# full.net
KiCad netlist of a schematic drawn in Altium Designer
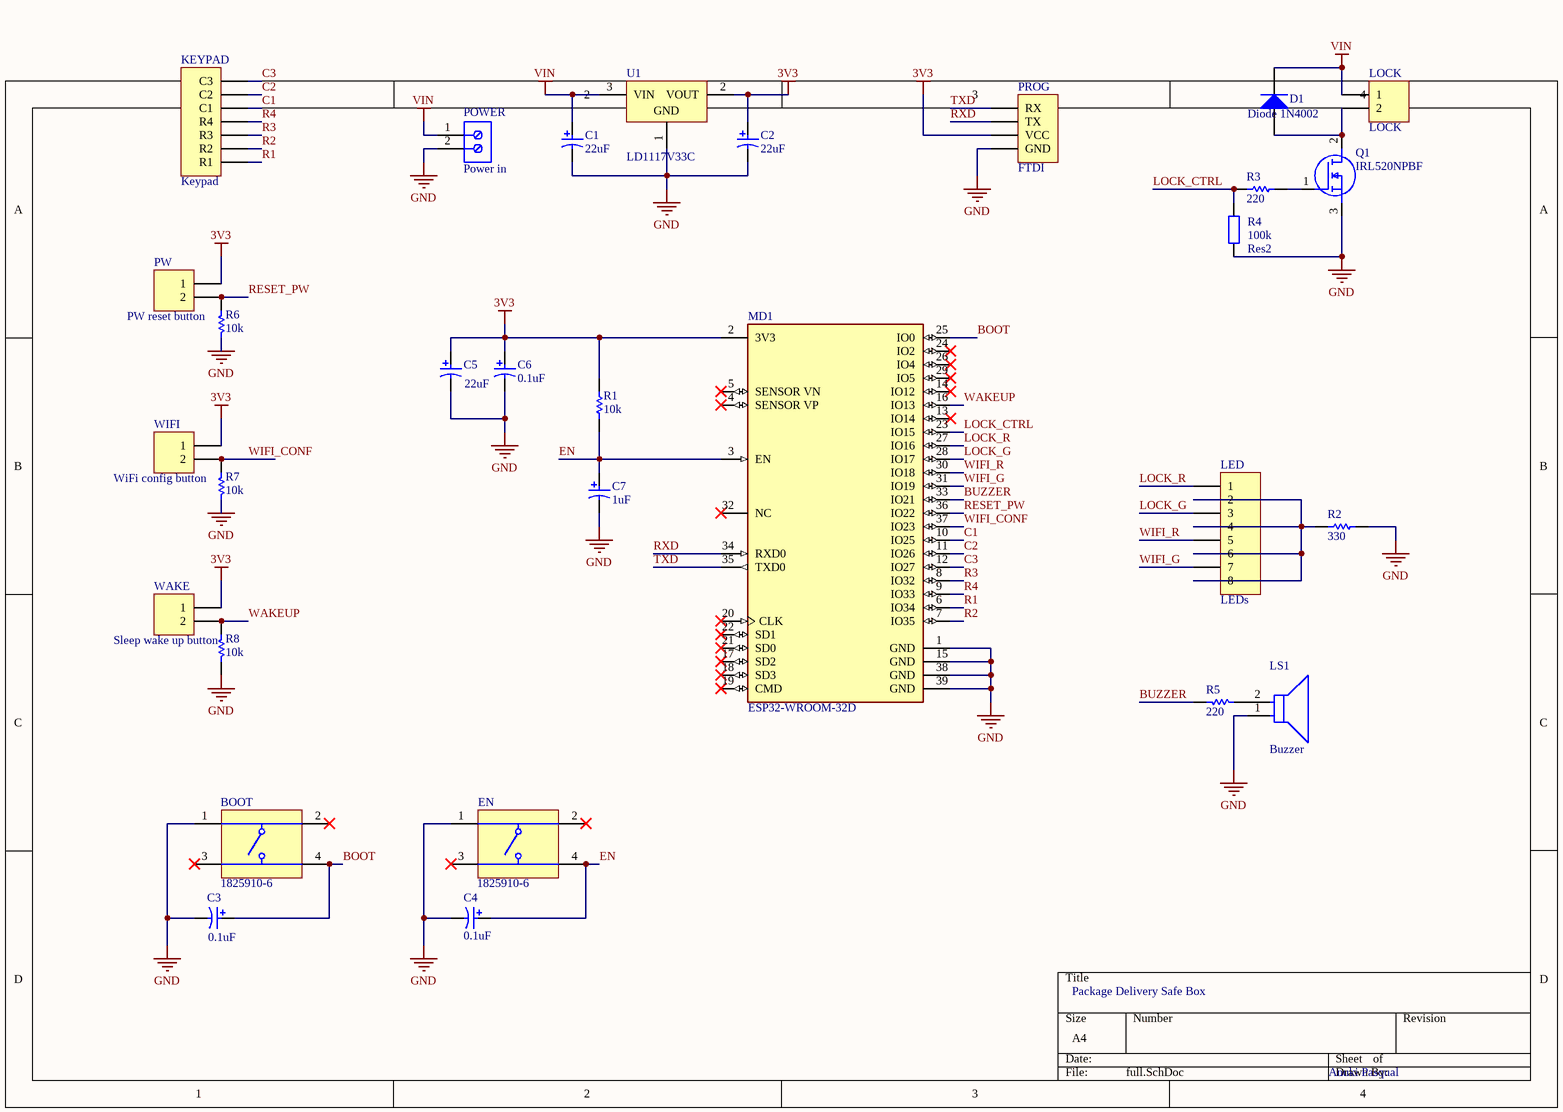
[diagram p0: full.SchDoc]

(export (version "E")
  (design (tool "Eeschema 10.0.6"))
  (components
    (comp (ref "BOOT")
      (value "1825910-6")
      (footprint "TECO-1825910-6_V")
      (description "Tact Switch, SPST-NO, 0.05 A, -35 to 85 degC, 4-Pin THD, RoHS, Bulk")
      (fields (field (name "MANUFACTURER") "TE Connectivity"))
      (libsource (lib "Altium Content Vault") (part "SW-SPST-4_A"))
    )
    (comp (ref "C1")
      (value "22uF")
      (footprint "CAPPR55-200-1100X500X1200")
      (description "Aluminum Electrolytic Capacitor, 22 uF, +/- 20%, 50 V, -40 to 85 degC, 2-Pin THD, RoHS, Bulk")
      (fields (field (name "VOLTAGE") "50V") (field (name "MANUFACTURER") "Panasonic"))
      (libsource (lib "Altium Content Vault") (part "CAP-P-2"))
    )
    (comp (ref "C2")
      (value "22uF")
      (footprint "CAPPR55-200-1100X500X1200")
      (description "Aluminum Electrolytic Capacitor, 22 uF, +/- 20%, 50 V, -40 to 85 degC, 2-Pin THD, RoHS, Bulk")
      (fields (field (name "VOLTAGE") "50V") (field (name "MANUFACTURER") "Panasonic"))
      (libsource (lib "Altium Content Vault") (part "CAP-P-2"))
    )
    (comp (ref "C3")
      (value "0.1uF")
      (footprint "CAPPR55-200-1100X500X1200")
      (description "Aluminum Electrolytic Capacitor, 22 uF, +/- 20%, 50 V, -40 to 85 degC, 2-Pin THD, RoHS, Bulk")
      (fields (field (name "VOLTAGE") "50V") (field (name "MANUFACTURER") "Panasonic"))
      (libsource (lib "Altium Content Vault") (part "CAP-P-2"))
    )
    (comp (ref "C4")
      (value "0.1uF")
      (footprint "CAPPR55-200-1100X500X1200")
      (description "Aluminum Electrolytic Capacitor, 22 uF, +/- 20%, 50 V, -40 to 85 degC, 2-Pin THD, RoHS, Bulk")
      (fields (field (name "VOLTAGE") "50V") (field (name "MANUFACTURER") "Panasonic"))
      (libsource (lib "Altium Content Vault") (part "CAP-P-2"))
    )
    (comp (ref "C5")
      (value "22uF")
      (footprint "CAPPR55-200-1100X500X1200")
      (description "Aluminum Electrolytic Capacitor, 22 uF, +/- 20%, 50 V, -40 to 85 degC, 2-Pin THD, RoHS, Bulk")
      (fields (field (name "VOLTAGE") "50V") (field (name "MANUFACTURER") "Panasonic"))
      (libsource (lib "Altium Content Vault") (part "CAP-P-2"))
    )
    (comp (ref "C6")
      (value "0.1uF")
      (footprint "CAPPR55-200-1100X500X1200")
      (description "Aluminum Electrolytic Capacitor, 22 uF, +/- 20%, 50 V, -40 to 85 degC, 2-Pin THD, RoHS, Bulk")
      (fields (field (name "VOLTAGE") "50V") (field (name "MANUFACTURER") "Panasonic"))
      (libsource (lib "Altium Content Vault") (part "CAP-P-2"))
    )
    (comp (ref "C7")
      (value "1uF")
      (footprint "CAPPR55-200-1100X500X1200")
      (description "Aluminum Electrolytic Capacitor, 22 uF, +/- 20%, 50 V, -40 to 85 degC, 2-Pin THD, RoHS, Bulk")
      (fields (field (name "VOLTAGE") "50V") (field (name "MANUFACTURER") "Panasonic"))
      (libsource (lib "Altium Content Vault") (part "CAP-P-2"))
    )
    (comp (ref "D1")
      (value "Diode 1N4002")
      (footprint "DO-41")
      (description "1 Amp General Purpose Rectifier")
      (fields (field (name "PUBLISHER") "Altium Limited"))
      (libsource (lib "Miscellaneous Devices") (part "Diode 1N4002"))
    )
    (comp (ref "EN")
      (value "1825910-6")
      (footprint "TECO-1825910-6_V")
      (description "Tact Switch, SPST-NO, 0.05 A, -35 to 85 degC, 4-Pin THD, RoHS, Bulk")
      (fields (field (name "MANUFACTURER") "TE Connectivity"))
      (libsource (lib "Altium Content Vault") (part "SW-SPST-4_A"))
    )
    (comp (ref "KEYPAD")
      (value "Keypad")
      (footprint "Miscellaneous Connectors:HDR1X7")
      (description "Header, 7-Pin")
      (fields (field (name "PUBLISHER") "Altium Limited"))
      (libsource (lib "Miscellaneous Connectors") (part "Header 7"))
    )
    (comp (ref "LED")
      (value "LEDs")
      (footprint "HDR1X8")
      (description "Header, 8-Pin")
      (fields (field (name "PUBLISHER") "Altium Limited"))
      (libsource (lib "Miscellaneous Connectors") (part "Header 8"))
    )
    (comp (ref "LOCK")
      (value "LOCK")
      (footprint "HDR1X2")
      (description "Header, 2-Pin")
      (fields (field (name "PUBLISHER") "Altium Limited"))
      (libsource (lib "") (part "Header 2_1"))
    )
    (comp (ref "LS1")
      (value "Buzzer")
      (footprint "FP-MCKPX-G1203A-K4056-MFG")
      (description "MAGNETIC BUZZER AND TRANSDUCER - More Details")
      (fields
        (field (name "MANUFACTURER PART NUMBER") "MCKPX-G1203A-K4056")
        (field (name "MANUFACTURER") "Multicomp Pro")
      )
      (libsource (lib "Altium Content Vault") (part "1973c4b650225fd2ddacaff6b763965"))
    )
    (comp (ref "MD1")
      (value "ESP32-WROOM-32D")
      (footprint "FP-ESP32-WROOM-32D-MFG")
      (description "WIFI MODULE 32MBITS SPI FLASH")
      (fields
        (field (name "OCTOPART") "https://octopart.com/esp32-wroom-32d-espressif+systems-91040050")
        (field (name "MANUFACTURER") "Espressif Systems")
      )
      (libsource (lib "Altium Content Vault") (part "a031a76f8c27026a7a7f4657ff233a3"))
    )
    (comp (ref "POWER")
      (value "Power in")
      (footprint "691102710002")
      (description "Series 102 - 5.00 mm Horizontal Entry Modular with Pressure Clamp WR-TBL, 2 pin")
      (fields
        (field (name "MANUFACTURER") "Wurth Elektronik")
        (field (name "PART NUMBER") "691102710002")
        (field (name "PUBLISHER") "WurthElektronik")
      )
      (libsource (lib "Altium Content Vault") (part "WE-CN-1P-F-TB2"))
    )
    (comp (ref "PROG")
      (value "FTDI")
      (footprint "HDR1X4")
      (description "Header, 4-Pin")
      (fields (field (name "PUBLISHER") "Altium Limited"))
      (libsource (lib "Miscellaneous Connectors") (part "Header 4"))
    )
    (comp (ref "PW")
      (value "PW reset button")
      (footprint "HDR1X2")
      (description "Header, 2-Pin")
      (fields (field (name "PUBLISHER") "Altium Limited"))
      (libsource (lib "Miscellaneous Connectors") (part "Header 2"))
    )
    (comp (ref "Q1")
      (value "IRL520NPBF")
      (footprint "SamacSys:TO254P469X1042X1967-3P")
      (description "MOSFET (N-Channel)")
      (fields (field (name "MOUSER PART NUMBER") "942-IRL520NPBF"))
      (libsource (lib "SamacSys") (part "IRL520NPBF"))
    )
    (comp (ref "R1")
      (value "10k")
      (footprint "AXIAL-0.3")
      (description "Resistor")
      (fields (field (name "PUBLISHER") "Altium Limited"))
      (libsource (lib "Miscellaneous Devices") (part "Res1"))
    )
    (comp (ref "R2")
      (value "330")
      (footprint "AXIAL-0.3")
      (description "Resistor")
      (fields (field (name "PUBLISHER") "Altium Limited"))
      (libsource (lib "Miscellaneous Devices") (part "Res1"))
    )
    (comp (ref "R3")
      (value "220")
      (footprint "AXIAL-0.3")
      (description "Resistor")
      (fields (field (name "PUBLISHER") "Altium Limited"))
      (libsource (lib "Miscellaneous Devices") (part "Res1"))
    )
    (comp (ref "R4")
      (value "Res2")
      (footprint "AXIAL-0.4")
      (description "Resistor")
      (fields (field (name "ALTIUM_VALUE") "100k") (field (name "PUBLISHER") "Altium Limited"))
      (libsource (lib "Miscellaneous Devices") (part "Res2"))
    )
    (comp (ref "R5")
      (value "220")
      (footprint "AXIAL-0.3")
      (description "Resistor")
      (fields (field (name "PUBLISHER") "Altium Limited"))
      (libsource (lib "Miscellaneous Devices") (part "Res1"))
    )
    (comp (ref "R6")
      (value "10k")
      (footprint "AXIAL-0.3")
      (description "Resistor")
      (fields (field (name "PUBLISHER") "Altium Limited"))
      (libsource (lib "Miscellaneous Devices") (part "Res1"))
    )
    (comp (ref "R7")
      (value "10k")
      (footprint "AXIAL-0.3")
      (description "Resistor")
      (fields (field (name "PUBLISHER") "Altium Limited"))
      (libsource (lib "Miscellaneous Devices") (part "Res1"))
    )
    (comp (ref "R8")
      (value "10k")
      (footprint "AXIAL-0.3")
      (description "Resistor")
      (fields (field (name "PUBLISHER") "Altium Limited"))
      (libsource (lib "Miscellaneous Devices") (part "Res1"))
    )
    (comp (ref "U1")
      (value "LD1117V33C")
      (footprint "TO220")
      (description "Fixed Low Drop Positive Voltage Regulator, 3.3V, 3-Pin TO-220")
      (libsource (lib "Altium Content Vault") (part "PM-REG-LD1117V-SIL3"))
    )
    (comp (ref "WAKE")
      (value "Sleep wake up button")
      (footprint "HDR1X2")
      (description "Header, 2-Pin")
      (fields (field (name "PUBLISHER") "Altium Limited"))
      (libsource (lib "Miscellaneous Connectors") (part "Header 2"))
    )
    (comp (ref "WIFI")
      (value "WiFi config button")
      (footprint "HDR1X2")
      (description "Header, 2-Pin")
      (fields (field (name "PUBLISHER") "Altium Limited"))
      (libsource (lib "Miscellaneous Connectors") (part "Header 2"))
    )
  )
  (nets
    (net (code "1") (name "/BOOT") (class "Default")
      (node (ref "BOOT") (pin "4") (pinfunction "4_4") (pintype "passive"))
      (node (ref "C3") (pin "1") (pinfunction "1_1") (pintype "passive"))
      (node (ref "MD1") (pin "25") (pinfunction "IO0_25") (pintype "bidirectional"))
    )
    (net (code "2") (name "/BUZZER") (class "Default")
      (node (ref "MD1") (pin "33") (pinfunction "IO21_33") (pintype "bidirectional"))
      (node (ref "R5") (pin "1") (pinfunction "1_1") (pintype "passive"))
    )
    (net (code "3") (name "/C1") (class "Default")
      (node (ref "KEYPAD") (pin "5") (pinfunction "C1_5") (pintype "passive"))
      (node (ref "MD1") (pin "10") (pinfunction "IO25_10") (pintype "bidirectional"))
    )
    (net (code "4") (name "/C2") (class "Default")
      (node (ref "KEYPAD") (pin "6") (pinfunction "C2_6") (pintype "passive"))
      (node (ref "MD1") (pin "11") (pinfunction "IO26_11") (pintype "bidirectional"))
    )
    (net (code "5") (name "/C3") (class "Default")
      (node (ref "KEYPAD") (pin "7") (pinfunction "C3_7") (pintype "passive"))
      (node (ref "MD1") (pin "12") (pinfunction "IO27_12") (pintype "bidirectional"))
    )
    (net (code "6") (name "/EN") (class "Default")
      (node (ref "C4") (pin "1") (pinfunction "1_1") (pintype "passive"))
      (node (ref "C7") (pin "1") (pinfunction "1_1") (pintype "passive"))
      (node (ref "EN") (pin "4") (pinfunction "4_4") (pintype "passive"))
      (node (ref "MD1") (pin "3") (pinfunction "EN_3") (pintype "input"))
      (node (ref "R1") (pin "1") (pinfunction "1_1") (pintype "passive"))
    )
    (net (code "7") (name "/LOCK_CTRL") (class "Default")
      (node (ref "MD1") (pin "23") (pinfunction "IO15_23") (pintype "bidirectional"))
      (node (ref "R3") (pin "2") (pinfunction "2_2") (pintype "passive"))
      (node (ref "R4") (pin "2") (pinfunction "2_2") (pintype "passive"))
    )
    (net (code "8") (name "/LOCK_G") (class "Default")
      (node (ref "LED") (pin "3") (pinfunction "3_3") (pintype "passive"))
      (node (ref "MD1") (pin "28") (pinfunction "IO17_28") (pintype "bidirectional"))
    )
    (net (code "9") (name "/LOCK_R") (class "Default")
      (node (ref "LED") (pin "1") (pinfunction "1_1") (pintype "passive"))
      (node (ref "MD1") (pin "27") (pinfunction "IO16_27") (pintype "bidirectional"))
    )
    (net (code "10") (name "/R1") (class "Default")
      (node (ref "KEYPAD") (pin "1") (pinfunction "R1_1") (pintype "passive"))
      (node (ref "MD1") (pin "6") (pinfunction "IO34_6") (pintype "bidirectional"))
    )
    (net (code "11") (name "/R2") (class "Default")
      (node (ref "KEYPAD") (pin "2") (pinfunction "R2_2") (pintype "passive"))
      (node (ref "MD1") (pin "7") (pinfunction "IO35_7") (pintype "bidirectional"))
    )
    (net (code "12") (name "/R3") (class "Default")
      (node (ref "KEYPAD") (pin "3") (pinfunction "R3_3") (pintype "passive"))
      (node (ref "MD1") (pin "8") (pinfunction "IO32_8") (pintype "bidirectional"))
    )
    (net (code "13") (name "/R4") (class "Default")
      (node (ref "KEYPAD") (pin "4") (pinfunction "R4_4") (pintype "passive"))
      (node (ref "MD1") (pin "9") (pinfunction "IO33_9") (pintype "bidirectional"))
    )
    (net (code "14") (name "/RESET_PW") (class "Default")
      (node (ref "MD1") (pin "36") (pinfunction "IO22_36") (pintype "bidirectional"))
      (node (ref "PW") (pin "2") (pinfunction "2_2") (pintype "passive"))
      (node (ref "R6") (pin "1") (pinfunction "1_1") (pintype "passive"))
    )
    (net (code "15") (name "/RXD") (class "Default")
      (node (ref "MD1") (pin "34") (pinfunction "RXD0_34") (pintype "input"))
      (node (ref "PROG") (pin "2") (pinfunction "TX_2") (pintype "passive"))
    )
    (net (code "16") (name "/TXD") (class "Default")
      (node (ref "MD1") (pin "35") (pinfunction "TXD0_35") (pintype "output"))
      (node (ref "PROG") (pin "1") (pinfunction "RX_1") (pintype "passive"))
    )
    (net (code "17") (name "/WAKEUP") (class "Default")
      (node (ref "MD1") (pin "16") (pinfunction "IO13_16") (pintype "bidirectional"))
      (node (ref "R8") (pin "1") (pinfunction "1_1") (pintype "passive"))
      (node (ref "WAKE") (pin "2") (pinfunction "2_2") (pintype "passive"))
    )
    (net (code "18") (name "/WIFI_CONF") (class "Default")
      (node (ref "MD1") (pin "37") (pinfunction "IO23_37") (pintype "bidirectional"))
      (node (ref "R7") (pin "1") (pinfunction "1_1") (pintype "passive"))
      (node (ref "WIFI") (pin "2") (pinfunction "2_2") (pintype "passive"))
    )
    (net (code "19") (name "/WIFI_G") (class "Default")
      (node (ref "LED") (pin "7") (pinfunction "7_7") (pintype "passive"))
      (node (ref "MD1") (pin "31") (pinfunction "IO19_31") (pintype "bidirectional"))
    )
    (net (code "20") (name "/WIFI_R") (class "Default")
      (node (ref "LED") (pin "5") (pinfunction "5_5") (pintype "passive"))
      (node (ref "MD1") (pin "30") (pinfunction "IO18_30") (pintype "bidirectional"))
    )
    (net (code "21") (name "3V3") (class "Default")
      (node (ref "C2") (pin "1") (pinfunction "1_1") (pintype "passive"))
      (node (ref "C5") (pin "1") (pinfunction "1_1") (pintype "passive"))
      (node (ref "C6") (pin "1") (pinfunction "1_1") (pintype "passive"))
      (node (ref "MD1") (pin "2") (pinfunction "3V3_2") (pintype "power_in"))
      (node (ref "PROG") (pin "3") (pinfunction "VCC_3") (pintype "passive"))
      (node (ref "PW") (pin "1") (pinfunction "1_1") (pintype "passive"))
      (node (ref "R1") (pin "2") (pinfunction "2_2") (pintype "passive"))
      (node (ref "U1") (pin "2") (pinfunction "VOUT_2") (pintype "power_in"))
      (node (ref "WAKE") (pin "1") (pinfunction "1_1") (pintype "passive"))
      (node (ref "WIFI") (pin "1") (pinfunction "1_1") (pintype "passive"))
    )
    (net (code "22") (name "GND") (class "Default")
      (node (ref "BOOT") (pin "1") (pinfunction "1_1") (pintype "passive"))
      (node (ref "C1") (pin "2") (pinfunction "2_2") (pintype "passive"))
      (node (ref "C2") (pin "2") (pinfunction "2_2") (pintype "passive"))
      (node (ref "C3") (pin "2") (pinfunction "2_2") (pintype "passive"))
      (node (ref "C4") (pin "2") (pinfunction "2_2") (pintype "passive"))
      (node (ref "C5") (pin "2") (pinfunction "2_2") (pintype "passive"))
      (node (ref "C6") (pin "2") (pinfunction "2_2") (pintype "passive"))
      (node (ref "C7") (pin "2") (pinfunction "2_2") (pintype "passive"))
      (node (ref "EN") (pin "1") (pinfunction "1_1") (pintype "passive"))
      (node (ref "LS1") (pin "1") (pinfunction "C_1") (pintype "passive"))
      (node (ref "MD1") (pin "1") (pinfunction "GND_1") (pintype "power_in"))
      (node (ref "MD1") (pin "15") (pinfunction "GND_15") (pintype "power_in"))
      (node (ref "MD1") (pin "38") (pinfunction "GND_38") (pintype "power_in"))
      (node (ref "MD1") (pin "39") (pinfunction "GND_39") (pintype "power_in"))
      (node (ref "POWER") (pin "2") (pinfunction "2_2") (pintype "passive"))
      (node (ref "PROG") (pin "4") (pinfunction "GND_4") (pintype "passive"))
      (node (ref "Q1") (pin "3") (pinfunction "S_3") (pintype "passive"))
      (node (ref "R2") (pin "2") (pinfunction "2_2") (pintype "passive"))
      (node (ref "R4") (pin "1") (pinfunction "1_1") (pintype "passive"))
      (node (ref "R6") (pin "2") (pinfunction "2_2") (pintype "passive"))
      (node (ref "R7") (pin "2") (pinfunction "2_2") (pintype "passive"))
      (node (ref "R8") (pin "2") (pinfunction "2_2") (pintype "passive"))
      (node (ref "U1") (pin "1") (pinfunction "GND_1") (pintype "power_in"))
    )
    (net (code "23") (name "Net-(D1-A)") (class "Default")
      (node (ref "D1") (pin "1") (pinfunction "A_1") (pintype "passive"))
      (node (ref "LOCK") (pin "2") (pinfunction "2_2") (pintype "passive"))
      (node (ref "Q1") (pin "2") (pinfunction "D_2") (pintype "passive"))
    )
    (net (code "24") (name "Net-(LED-Pad2)") (class "Default")
      (node (ref "LED") (pin "2") (pinfunction "2_2") (pintype "passive"))
      (node (ref "LED") (pin "4") (pinfunction "4_4") (pintype "passive"))
      (node (ref "LED") (pin "6") (pinfunction "6_6") (pintype "passive"))
      (node (ref "LED") (pin "8") (pinfunction "8_8") (pintype "passive"))
      (node (ref "R2") (pin "1") (pinfunction "1_1") (pintype "passive"))
    )
    (net (code "25") (name "Net-(LS1-A)") (class "Default")
      (node (ref "LS1") (pin "2") (pinfunction "A_2") (pintype "passive"))
      (node (ref "R5") (pin "2") (pinfunction "2_2") (pintype "passive"))
    )
    (net (code "26") (name "Net-(Q1-G)") (class "Default")
      (node (ref "Q1") (pin "1") (pinfunction "G_1") (pintype "passive"))
      (node (ref "R3") (pin "1") (pinfunction "1_1") (pintype "passive"))
    )
    (net (code "27") (name "VIN") (class "Default")
      (node (ref "C1") (pin "1") (pinfunction "1_1") (pintype "passive"))
      (node (ref "D1") (pin "2") (pinfunction "K_2") (pintype "passive"))
      (node (ref "LOCK") (pin "1") (pinfunction "1_1") (pintype "passive"))
      (node (ref "POWER") (pin "1") (pinfunction "1_1") (pintype "passive"))
      (node (ref "U1") (pin "3") (pinfunction "VIN_3") (pintype "power_in"))
    )
    (net (code "28") (name "unconnected-(BOOT-Pad2)") (class "Default")
      (node (ref "BOOT") (pin "2") (pinfunction "2_2") (pintype "passive+no_connect"))
    )
    (net (code "29") (name "unconnected-(BOOT-Pad3)") (class "Default")
      (node (ref "BOOT") (pin "3") (pinfunction "3_3") (pintype "passive+no_connect"))
    )
    (net (code "30") (name "unconnected-(EN-Pad2)") (class "Default")
      (node (ref "EN") (pin "2") (pinfunction "2_2") (pintype "passive+no_connect"))
    )
    (net (code "31") (name "unconnected-(EN-Pad3)") (class "Default")
      (node (ref "EN") (pin "3") (pinfunction "3_3") (pintype "passive+no_connect"))
    )
    (net (code "32") (name "unconnected-(MD1-CLK-Pad20)") (class "Default")
      (node (ref "MD1") (pin "20") (pinfunction "CLK_20") (pintype "input+no_connect"))
    )
    (net (code "33") (name "unconnected-(MD1-CMD-Pad19)") (class "Default")
      (node (ref "MD1") (pin "19") (pinfunction "CMD_19") (pintype "bidirectional+no_connect"))
    )
    (net (code "34") (name "unconnected-(MD1-IO2-Pad24)") (class "Default")
      (node (ref "MD1") (pin "24") (pinfunction "IO2_24") (pintype "bidirectional+no_connect"))
    )
    (net (code "35") (name "unconnected-(MD1-IO4-Pad26)") (class "Default")
      (node (ref "MD1") (pin "26") (pinfunction "IO4_26") (pintype "bidirectional+no_connect"))
    )
    (net (code "36") (name "unconnected-(MD1-IO5-Pad29)") (class "Default")
      (node (ref "MD1") (pin "29") (pinfunction "IO5_29") (pintype "bidirectional+no_connect"))
    )
    (net (code "37") (name "unconnected-(MD1-IO12-Pad14)") (class "Default")
      (node (ref "MD1") (pin "14") (pinfunction "IO12_14") (pintype "bidirectional+no_connect"))
    )
    (net (code "38") (name "unconnected-(MD1-IO14-Pad13)") (class "Default")
      (node (ref "MD1") (pin "13") (pinfunction "IO14_13") (pintype "bidirectional+no_connect"))
    )
    (net (code "39") (name "unconnected-(MD1-NC-Pad32)") (class "Default")
      (node (ref "MD1") (pin "32") (pinfunction "NC_32") (pintype "passive+no_connect"))
    )
    (net (code "40") (name "unconnected-(MD1-SD0-Pad21)") (class "Default")
      (node (ref "MD1") (pin "21") (pinfunction "SD0_21") (pintype "bidirectional+no_connect"))
    )
    (net (code "41") (name "unconnected-(MD1-SD1-Pad22)") (class "Default")
      (node (ref "MD1") (pin "22") (pinfunction "SD1_22") (pintype "bidirectional+no_connect"))
    )
    (net (code "42") (name "unconnected-(MD1-SD2-Pad17)") (class "Default")
      (node (ref "MD1") (pin "17") (pinfunction "SD2_17") (pintype "bidirectional+no_connect"))
    )
    (net (code "43") (name "unconnected-(MD1-SD3-Pad18)") (class "Default")
      (node (ref "MD1") (pin "18") (pinfunction "SD3_18") (pintype "bidirectional+no_connect"))
    )
    (net (code "44") (name "unconnected-(MD1-SENSOR_VN-Pad5)") (class "Default")
      (node (ref "MD1") (pin "5") (pinfunction "SENSOR_VN_5") (pintype "bidirectional+no_connect"))
    )
    (net (code "45") (name "unconnected-(MD1-SENSOR_VP-Pad4)") (class "Default")
      (node (ref "MD1") (pin "4") (pinfunction "SENSOR_VP_4") (pintype "bidirectional+no_connect"))
    )
  )
)
